# NinjaPCB-ver1_0.net
KiCad netlist of a schematic drawn in EAGLE
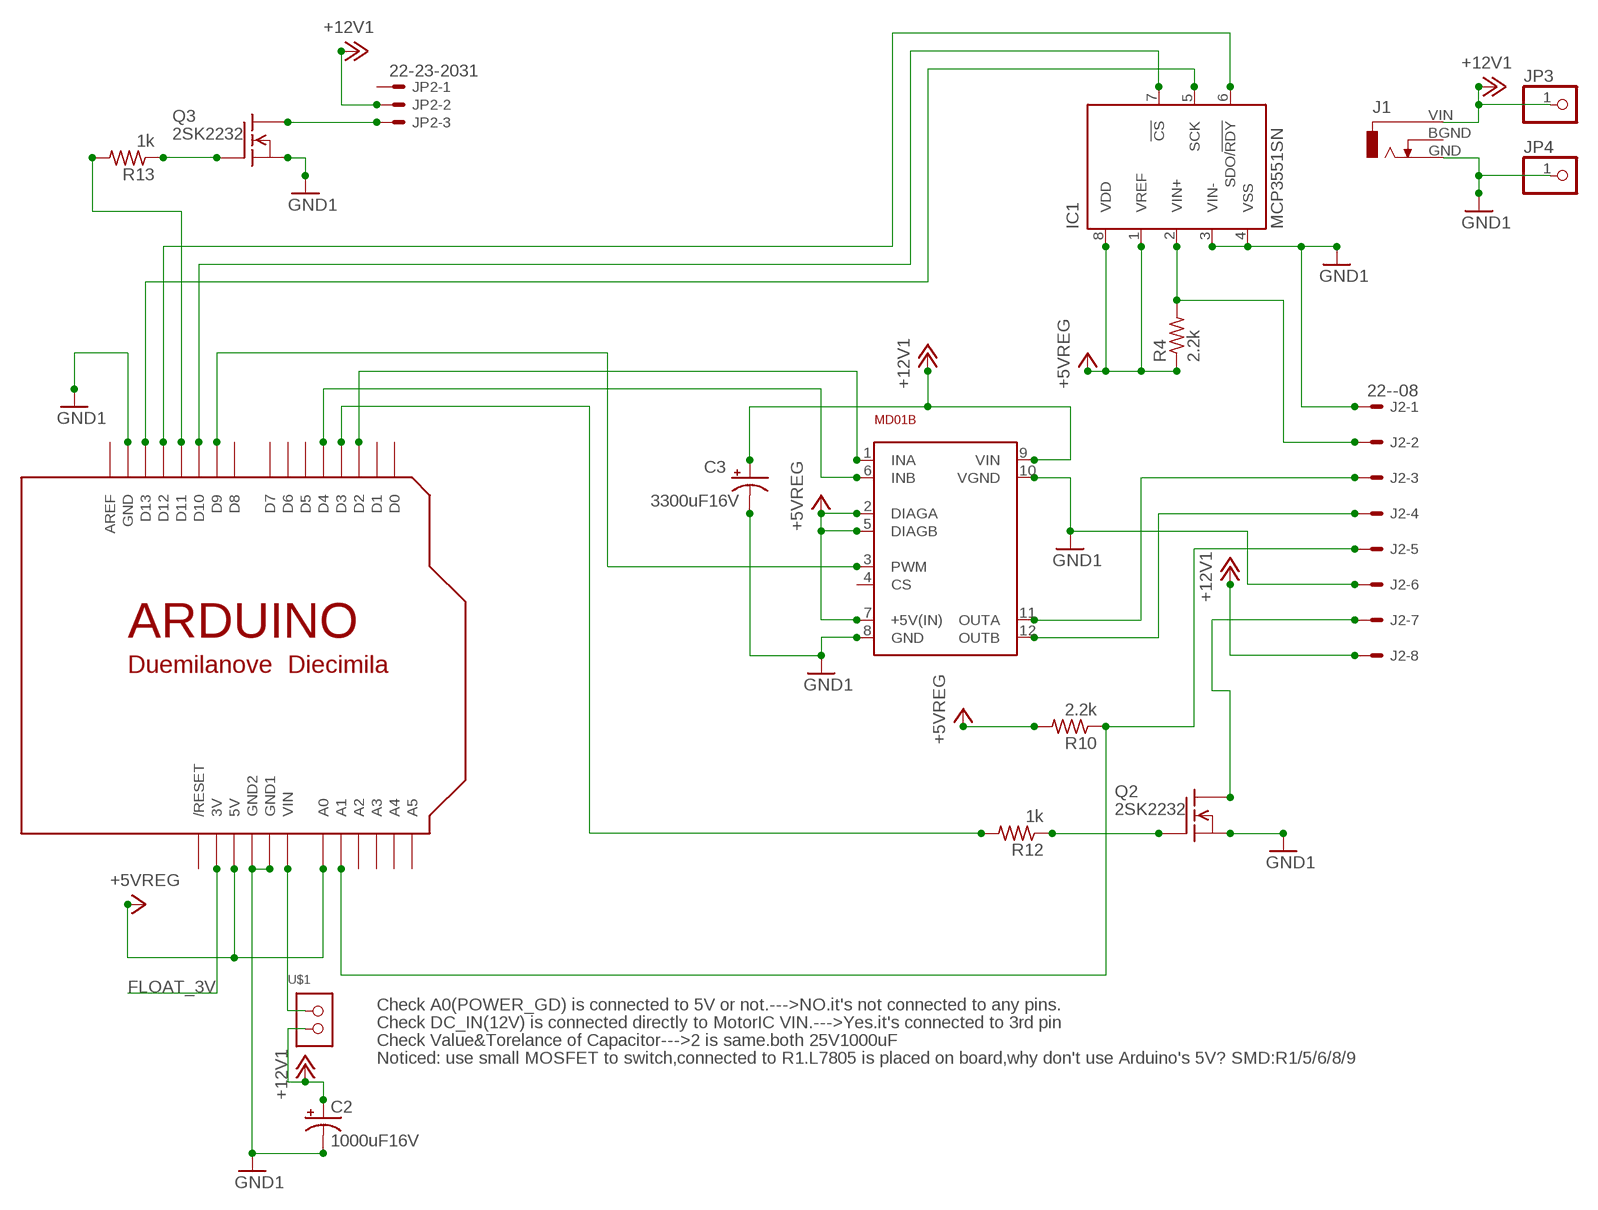
[diagram p0: schematic, sheet 1]

(export (version "E")
  (design (tool "Eeschema 10.0.6"))
  (components
    (comp (ref "C2")
      (value "1000uF16V")
      (footprint "eagle-import:E5-8,5")
      (libsource (lib "eagle-import") (part "CPOL-USE5-8.5"))
    )
    (comp (ref "C3")
      (value "3300uF16V")
      (footprint "eagle-import:E5-13")
      (libsource (lib "eagle-import") (part "CPOL-USE5-13"))
    )
    (comp (ref "IC1")
      (value "MCP3551SN")
      (footprint "eagle-import:SO-08")
      (fields (field (name "MPN") "MCP3551-E/SN"))
      (libsource (lib "eagle-import") (part "MCP355SN1"))
    )
    (comp (ref "J1")
      (value "DCJ0303")
      (footprint "eagle-import:DCJ0303")
      (libsource (lib "eagle-import") (part "DCJ0303"))
    )
    (comp (ref "J2")
      (value "22--08")
      (footprint "eagle-import:POLOLU-8-VERTICAL")
      (libsource (lib "eagle-import") (part "22-?-08"))
    )
    (comp (ref "JP2")
      (value "22-23-2031")
      (footprint "eagle-import:22-23-2031")
      (fields (field (name "MF") "MOLEX"))
      (libsource (lib "eagle-import") (part "22-23-2031"))
    )
    (comp (ref "JP3")
      (value "PINHD-1X1")
      (footprint "eagle-import:1X01")
      (libsource (lib "eagle-import") (part "PINHD-1X1"))
    )
    (comp (ref "JP4")
      (value "PINHD-1X1")
      (footprint "eagle-import:1X01")
      (libsource (lib "eagle-import") (part "PINHD-1X1"))
    )
    (comp (ref "MD01B")
      (value "VNH3SP30+4PINN")
      (footprint "eagle-import:VNH3SP30+4PIN_NOHOLES")
      (libsource (lib "eagle-import") (part "VNH3SP30+4PINN"))
    )
    (comp (ref "Q2")
      (value "2SK2232")
      (footprint "eagle-import:TO202")
      (libsource (lib "eagle-import") (part "BSS97"))
    )
    (comp (ref "Q3")
      (value "2SK2232")
      (footprint "eagle-import:TO202")
      (libsource (lib "eagle-import") (part "BSS97"))
    )
    (comp (ref "R4")
      (value "2.2k")
      (footprint "eagle-import:0207_10")
      (libsource (lib "eagle-import") (part "R-US_0207/10"))
    )
    (comp (ref "R10")
      (value "2.2k")
      (footprint "eagle-import:0207_10")
      (libsource (lib "eagle-import") (part "R-US_0207/10"))
    )
    (comp (ref "R12")
      (value "1k")
      (footprint "eagle-import:0207_10")
      (libsource (lib "eagle-import") (part "R-US_0207/10"))
    )
    (comp (ref "R13")
      (value "1k")
      (footprint "eagle-import:0207_10")
      (libsource (lib "eagle-import") (part "R-US_0207/10"))
    )
    (comp (ref "U$1")
      (value "1X02")
      (footprint "eagle-import:1X02_1.1_UNSIGNED")
      (libsource (lib "eagle-import") (part "1X02"))
    )
    (comp (ref "U$3")
      (value "Arduino UNO")
      (footprint "eagle-import:ARDUINO-NOSILK")
      (libsource (lib "eagle-import") (part "ARDUINONS"))
    )
  )
  (nets
    (net (code "1") (name "+5VREG") (class "Default")
      (node (ref "IC1") (pin "1") (pinfunction "VREF_1") (pintype "input"))
      (node (ref "IC1") (pin "8") (pinfunction "VDD_8") (pintype "power_in"))
      (node (ref "MD01B") (pin "2") (pinfunction "DIAGA_2") (pintype "passive"))
      (node (ref "MD01B") (pin "5") (pinfunction "DIAGB_5") (pintype "passive"))
      (node (ref "MD01B") (pin "7") (pinfunction "+5V(IN)_7") (pintype "power_in"))
      (node (ref "R10") (pin "2") (pinfunction "2_2") (pintype "passive"))
      (node (ref "R4") (pin "1") (pinfunction "1_1") (pintype "passive"))
      (node (ref "U$3") (pin "5V") (pinfunction "5V_5V") (pintype "power_in"))
      (node (ref "U$3") (pin "A0") (pinfunction "A0_A0") (pintype "bidirectional"))
    )
    (net (code "2") (name "+12V1") (class "Default")
      (node (ref "C2") (pin "+") (pinfunction "+_+") (pintype "passive"))
      (node (ref "C3") (pin "+") (pinfunction "+_+") (pintype "passive"))
      (node (ref "J1") (pin "VIN") (pinfunction "VIN_VIN") (pintype "passive"))
      (node (ref "J2") (pin "8") (pinfunction "S_8") (pintype "passive"))
      (node (ref "JP2") (pin "2") (pinfunction "S_2") (pintype "passive"))
      (node (ref "JP3") (pin "1") (pinfunction "1_1") (pintype "passive"))
      (node (ref "MD01B") (pin "9") (pinfunction "VIN_9") (pintype "power_in"))
      (node (ref "U$1") (pin "2") (pinfunction "2_2") (pintype "passive"))
    )
    (net (code "3") (name "/FLOAT_3V") (class "Default")
      (node (ref "U$3") (pin "3V") (pinfunction "3V_3V") (pintype "power_in"))
    )
    (net (code "4") (name "GND1") (class "Default")
      (node (ref "C2") (pin "-") (pinfunction "-_-") (pintype "passive"))
      (node (ref "C3") (pin "-") (pinfunction "-_-") (pintype "passive"))
      (node (ref "IC1") (pin "3") (pinfunction "VIN-_3") (pintype "input"))
      (node (ref "IC1") (pin "4") (pinfunction "VSS_4") (pintype "power_in"))
      (node (ref "J1") (pin "GND") (pinfunction "GND_GND") (pintype "passive"))
      (node (ref "J2") (pin "1") (pinfunction "S_1") (pintype "passive"))
      (node (ref "J2") (pin "6") (pinfunction "S_6") (pintype "passive"))
      (node (ref "JP4") (pin "1") (pinfunction "1_1") (pintype "passive"))
      (node (ref "MD01B") (pin "10") (pinfunction "VGND_10") (pintype "power_in"))
      (node (ref "MD01B") (pin "8") (pinfunction "GND_8") (pintype "power_in"))
      (node (ref "Q2") (pin "1") (pinfunction "S_1") (pintype "passive"))
      (node (ref "Q3") (pin "1") (pinfunction "S_1") (pintype "passive"))
      (node (ref "U$3") (pin "GND") (pinfunction "GND_GND") (pintype "power_in"))
      (node (ref "U$3") (pin "GND1") (pinfunction "GND1_GND1") (pintype "power_in"))
      (node (ref "U$3") (pin "GND2") (pinfunction "GND2_GND2") (pintype "power_in"))
    )
    (net (code "5") (name "Net-(IC1-SCK)") (class "Default")
      (node (ref "IC1") (pin "5") (pinfunction "SCK_5") (pintype "input"))
      (node (ref "U$3") (pin "D13") (pinfunction "D13_D13") (pintype "bidirectional"))
    )
    (net (code "6") (name "Net-(IC1-SDO{slash}~{RDY})") (class "Default")
      (node (ref "IC1") (pin "6") (pinfunction "SDO/~{RDY}_6") (pintype "output"))
      (node (ref "U$3") (pin "D12") (pinfunction "D12_D12") (pintype "bidirectional"))
    )
    (net (code "7") (name "Net-(IC1-VIN+)") (class "Default")
      (node (ref "IC1") (pin "2") (pinfunction "VIN+_2") (pintype "input"))
      (node (ref "J2") (pin "2") (pinfunction "S_2") (pintype "passive"))
      (node (ref "R4") (pin "2") (pinfunction "2_2") (pintype "passive"))
    )
    (net (code "8") (name "Net-(IC1-~{CS})") (class "Default")
      (node (ref "IC1") (pin "7") (pinfunction "~{CS}_7") (pintype "input"))
      (node (ref "U$3") (pin "D10") (pinfunction "D10_D10") (pintype "bidirectional"))
    )
    (net (code "9") (name "Net-(J2C-S)") (class "Default")
      (node (ref "J2") (pin "3") (pinfunction "S_3") (pintype "passive"))
      (node (ref "MD01B") (pin "11") (pinfunction "OUTA_11") (pintype "passive"))
    )
    (net (code "10") (name "Net-(J2D-S)") (class "Default")
      (node (ref "J2") (pin "4") (pinfunction "S_4") (pintype "passive"))
      (node (ref "MD01B") (pin "12") (pinfunction "OUTB_12") (pintype "passive"))
    )
    (net (code "11") (name "Net-(J2E-S)") (class "Default")
      (node (ref "J2") (pin "5") (pinfunction "S_5") (pintype "passive"))
      (node (ref "R10") (pin "1") (pinfunction "1_1") (pintype "passive"))
      (node (ref "U$3") (pin "A1") (pinfunction "A1_A1") (pintype "bidirectional"))
    )
    (net (code "12") (name "Net-(J2G-S)") (class "Default")
      (node (ref "J2") (pin "7") (pinfunction "S_7") (pintype "passive"))
      (node (ref "Q2") (pin "2") (pinfunction "D_2") (pintype "passive"))
    )
    (net (code "13") (name "Net-(JP2C-S)") (class "Default")
      (node (ref "JP2") (pin "3") (pinfunction "S_3") (pintype "passive"))
      (node (ref "Q3") (pin "2") (pinfunction "D_2") (pintype "passive"))
    )
    (net (code "14") (name "Net-(MD01B-INA)") (class "Default")
      (node (ref "MD01B") (pin "1") (pinfunction "INA_1") (pintype "passive"))
      (node (ref "U$3") (pin "D2") (pinfunction "D2_D2") (pintype "bidirectional"))
    )
    (net (code "15") (name "Net-(MD01B-INB)") (class "Default")
      (node (ref "MD01B") (pin "6") (pinfunction "INB_6") (pintype "passive"))
      (node (ref "U$3") (pin "D4") (pinfunction "D4_D4") (pintype "bidirectional"))
    )
    (net (code "16") (name "Net-(MD01B-PWM)") (class "Default")
      (node (ref "MD01B") (pin "3") (pinfunction "PWM_3") (pintype "passive"))
      (node (ref "U$3") (pin "D9") (pinfunction "D9_D9") (pintype "bidirectional"))
    )
    (net (code "17") (name "Net-(Q2-G)") (class "Default")
      (node (ref "Q2") (pin "3") (pinfunction "G_3") (pintype "passive"))
      (node (ref "R12") (pin "1") (pinfunction "1_1") (pintype "passive"))
    )
    (net (code "18") (name "Net-(Q3-G)") (class "Default")
      (node (ref "Q3") (pin "3") (pinfunction "G_3") (pintype "passive"))
      (node (ref "R13") (pin "1") (pinfunction "1_1") (pintype "passive"))
    )
    (net (code "19") (name "Net-(R12-Pad2)") (class "Default")
      (node (ref "R12") (pin "2") (pinfunction "2_2") (pintype "passive"))
      (node (ref "U$3") (pin "D3") (pinfunction "D3_D3") (pintype "bidirectional"))
    )
    (net (code "20") (name "Net-(R13-Pad2)") (class "Default")
      (node (ref "R13") (pin "2") (pinfunction "2_2") (pintype "passive"))
      (node (ref "U$3") (pin "D11") (pinfunction "D11_D11") (pintype "bidirectional"))
    )
    (net (code "21") (name "Net-(U$1-Pad1)") (class "Default")
      (node (ref "U$1") (pin "1") (pinfunction "1_1") (pintype "passive"))
      (node (ref "U$3") (pin "VIN") (pinfunction "VIN_VIN") (pintype "power_in"))
    )
    (net (code "22") (name "unconnected-(J1-PadBGND)") (class "Default")
      (node (ref "J1") (pin "BGND") (pinfunction "BGND_BGND") (pintype "passive"))
    )
    (net (code "23") (name "unconnected-(JP2A-S-Pad1)") (class "Default")
      (node (ref "JP2") (pin "1") (pinfunction "S_1") (pintype "passive"))
    )
    (net (code "24") (name "unconnected-(MD01B-CS-Pad4)") (class "Default")
      (node (ref "MD01B") (pin "4") (pinfunction "CS_4") (pintype "passive"))
    )
    (net (code "25") (name "unconnected-(U$3-PadA2)") (class "Default")
      (node (ref "U$3") (pin "A2") (pinfunction "A2_A2") (pintype "bidirectional"))
    )
    (net (code "26") (name "unconnected-(U$3-PadA3)") (class "Default")
      (node (ref "U$3") (pin "A3") (pinfunction "A3_A3") (pintype "bidirectional"))
    )
    (net (code "27") (name "unconnected-(U$3-PadA4)") (class "Default")
      (node (ref "U$3") (pin "A4") (pinfunction "A4_A4") (pintype "bidirectional"))
    )
    (net (code "28") (name "unconnected-(U$3-PadA5)") (class "Default")
      (node (ref "U$3") (pin "A5") (pinfunction "A5_A5") (pintype "bidirectional"))
    )
    (net (code "29") (name "unconnected-(U$3-PadAREF)") (class "Default")
      (node (ref "U$3") (pin "AREF") (pinfunction "AREF_AREF") (pintype "bidirectional"))
    )
    (net (code "30") (name "unconnected-(U$3-PadD0)") (class "Default")
      (node (ref "U$3") (pin "D0") (pinfunction "D0_D0") (pintype "bidirectional"))
    )
    (net (code "31") (name "unconnected-(U$3-PadD1)") (class "Default")
      (node (ref "U$3") (pin "D1") (pinfunction "D1_D1") (pintype "bidirectional"))
    )
    (net (code "32") (name "unconnected-(U$3-PadD5)") (class "Default")
      (node (ref "U$3") (pin "D5") (pinfunction "D5_D5") (pintype "bidirectional"))
    )
    (net (code "33") (name "unconnected-(U$3-PadD6)") (class "Default")
      (node (ref "U$3") (pin "D6") (pinfunction "D6_D6") (pintype "bidirectional"))
    )
    (net (code "34") (name "unconnected-(U$3-PadD7)") (class "Default")
      (node (ref "U$3") (pin "D7") (pinfunction "D7_D7") (pintype "bidirectional"))
    )
    (net (code "35") (name "unconnected-(U$3-PadD8)") (class "Default")
      (node (ref "U$3") (pin "D8") (pinfunction "D8_D8") (pintype "bidirectional"))
    )
    (net (code "36") (name "unconnected-(U$3-{slash}RESET-PadRESET)") (class "Default")
      (node (ref "U$3") (pin "RESET") (pinfunction "/RESET_RESET") (pintype "bidirectional"))
    )
  )
)
